# TPS5430.net
KiCad netlist of a schematic drawn in EasyEDA Pro
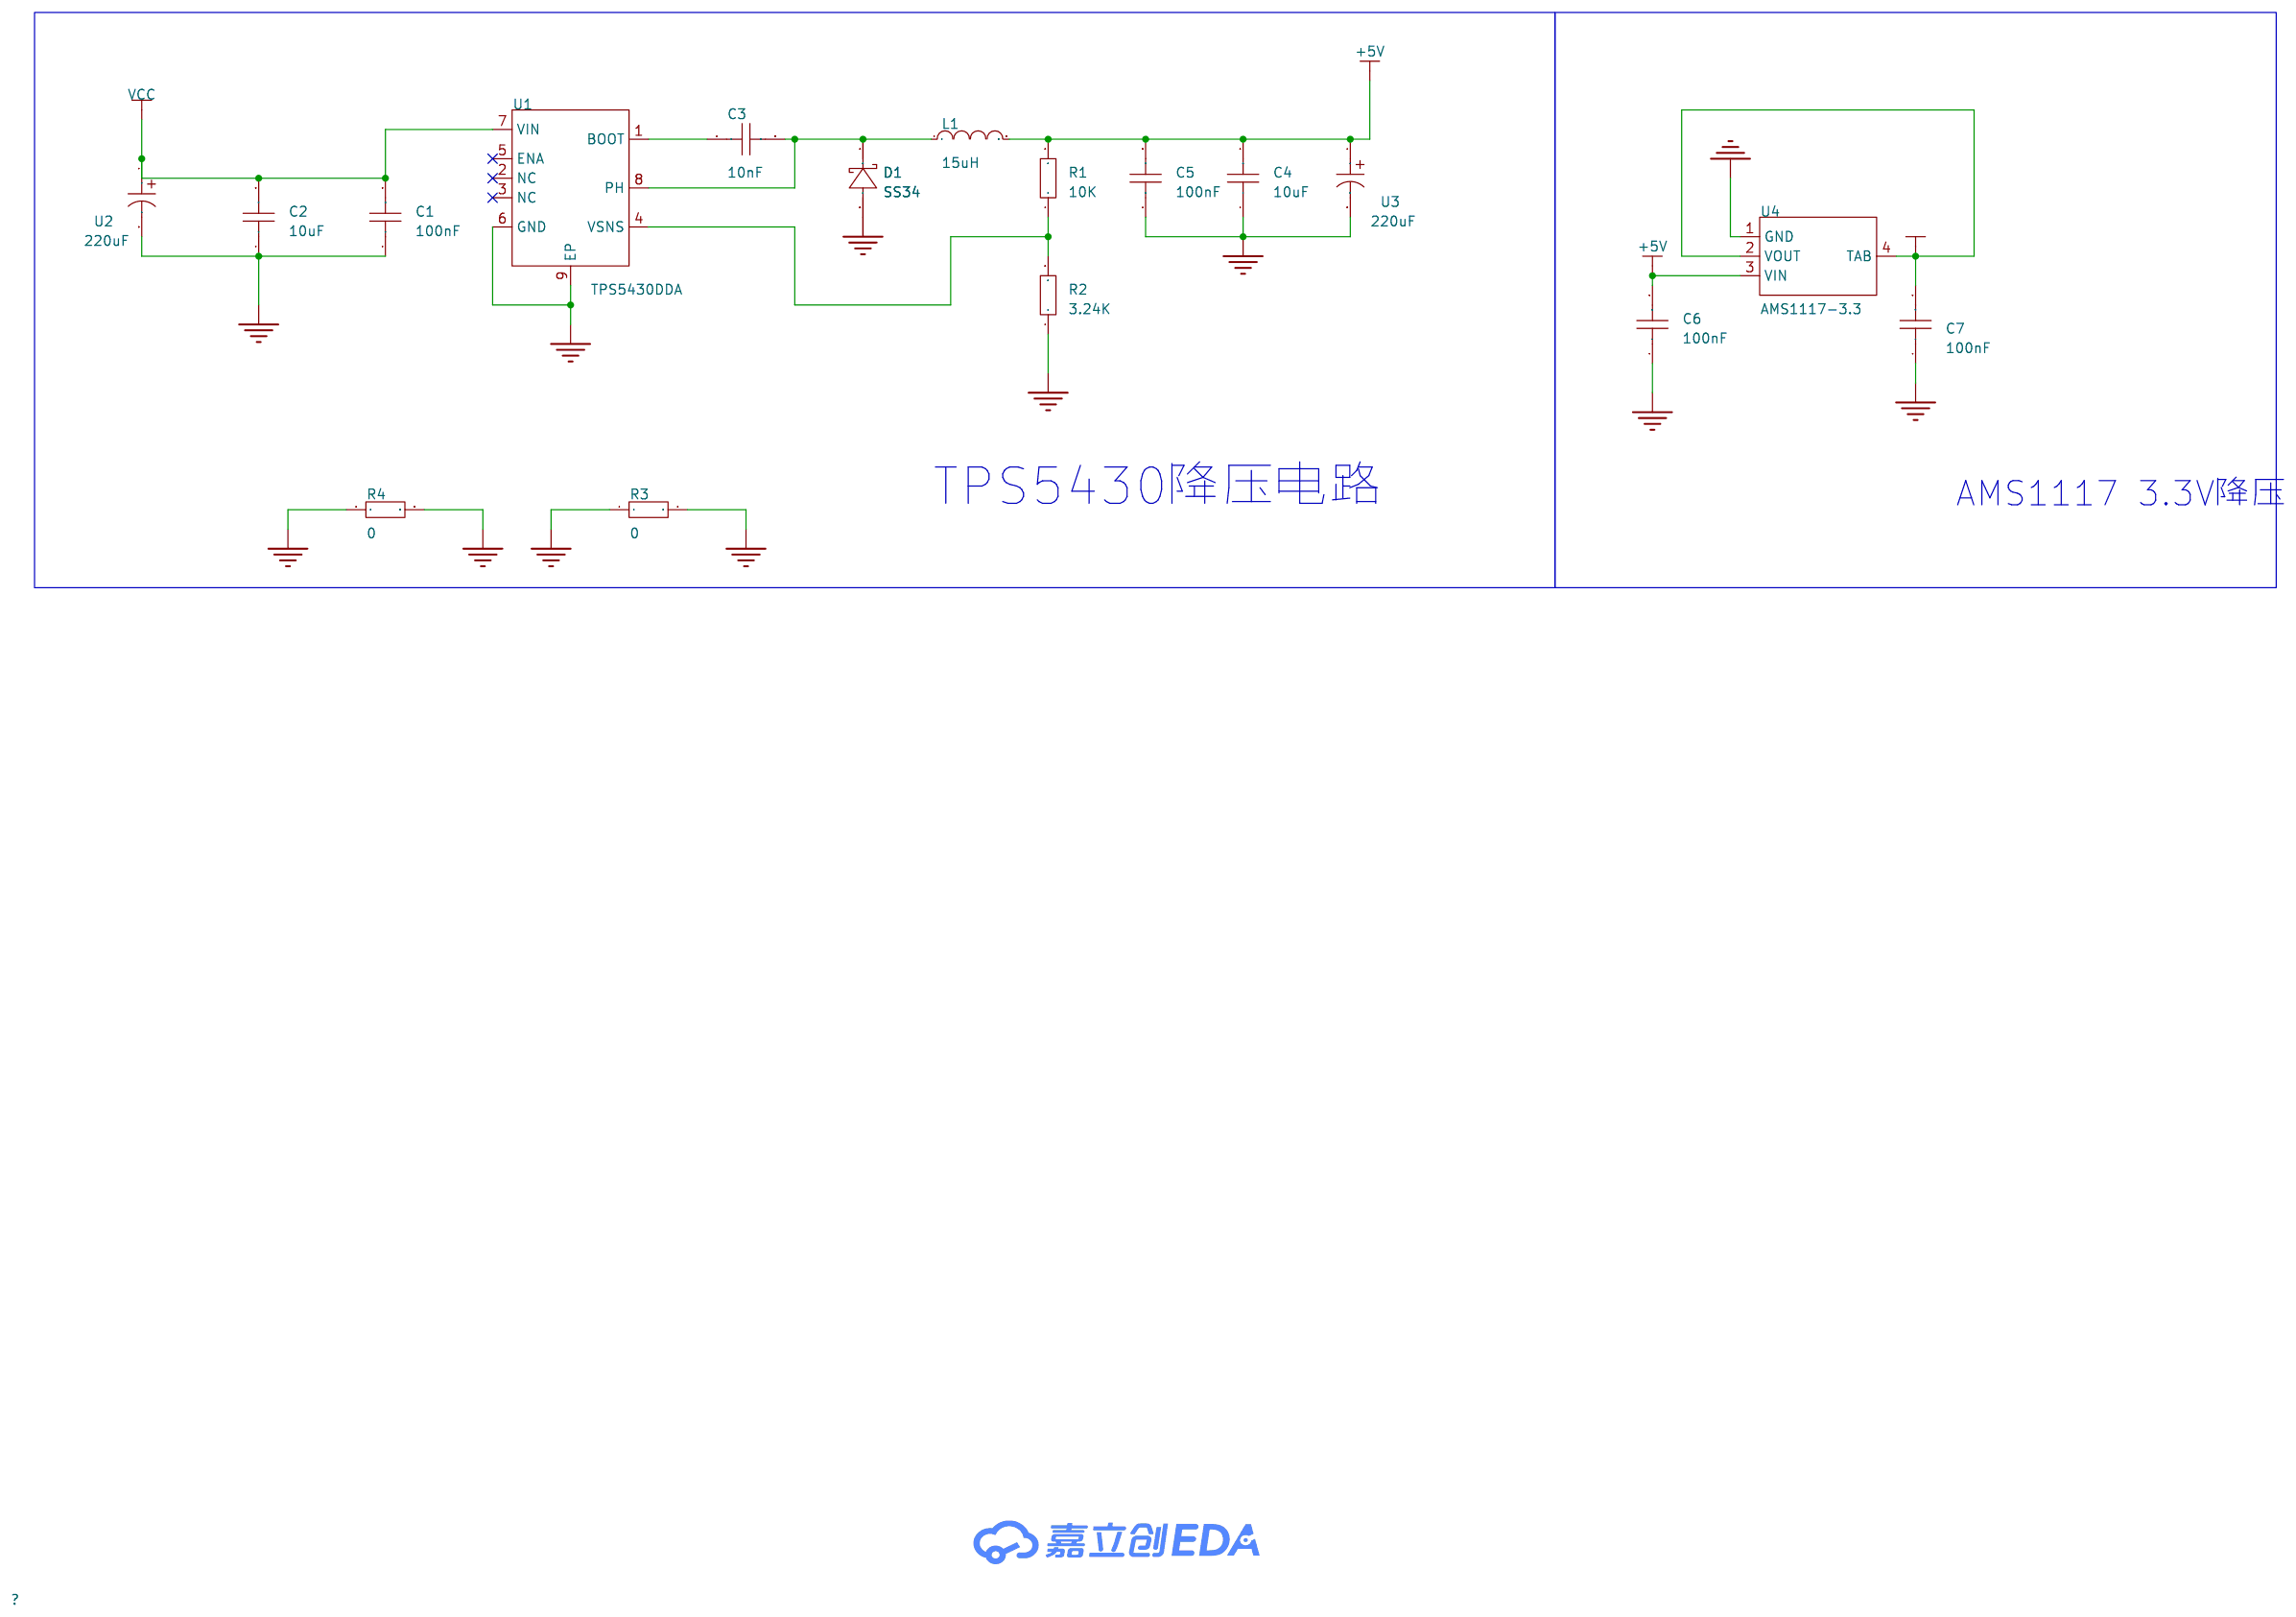
[diagram p0: schematic sheet]

(export (version "E")
  (design (tool "Eeschema 10.0.6"))
  (components
    (comp (ref "C1")
      (value "100nF")
      (footprint "easyedapro:C0603")
      (libsource (lib "easyedapro") (part "Capacitance"))
    )
    (comp (ref "C2")
      (value "10uF")
      (footprint "easyedapro:C0603")
      (libsource (lib "easyedapro") (part "Capacitance"))
    )
    (comp (ref "C3")
      (value "10nF")
      (footprint "easyedapro:C0402")
      (description "容值:100nF;精度:±10%;额定电压:50V;温度系数:X7R;")
      (fields
        (field (name "Manufacturer Part") "CL05B104KB54PNC")
        (field (name "Manufacturer") "SAMSUNG(三星)")
      )
      (libsource (lib "easyedapro") (part "CL05B104KB54PNC"))
    )
    (comp (ref "C4")
      (value "10uF")
      (footprint "easyedapro:C0603")
      (libsource (lib "easyedapro") (part "Capacitance"))
    )
    (comp (ref "C5")
      (value "100nF")
      (footprint "easyedapro:C0603")
      (libsource (lib "easyedapro") (part "Capacitance"))
    )
    (comp (ref "C6")
      (value "100nF")
      (footprint "easyedapro:C0402")
      (description "容值:100nF;精度:±10%;额定电压:50V;温度系数:X7R;")
      (fields
        (field (name "Manufacturer Part") "CL05B104KB54PNC")
        (field (name "Manufacturer") "SAMSUNG(三星)")
      )
      (libsource (lib "easyedapro") (part "CL05B104KB54PNC"))
    )
    (comp (ref "C7")
      (value "100nF")
      (footprint "easyedapro:C0402")
      (description "容值:100nF;精度:±10%;额定电压:50V;温度系数:X7R;")
      (fields
        (field (name "Manufacturer Part") "CL05B104KB54PNC")
        (field (name "Manufacturer") "SAMSUNG(三星)")
      )
      (libsource (lib "easyedapro") (part "CL05B104KB54PNC"))
    )
    (comp (ref "D1")
      (value "SS34")
      (footprint "easyedapro:SMA_L4.3-W2.5-LS5.0-RD")
      (description "二极管配置:独立式;正向压降(Vf):550mV@3A;直流反向耐压(Vr):40V;整流电流:3A;")
      (fields (field (name "Manufacturer") "TWGMC(台湾迪嘉)"))
      (libsource (lib "easyedapro") (part "SS34_C727060"))
    )
    (comp (ref "L1")
      (value "15uH")
      (footprint "easyedapro:IND-SMD_L7.0-W6.6_FXL0630")
      (description "电感值:15uH;精度:±20%;额定电流:3A;饱和电流(Isat):4A;类型:一体成型电感;")
      (fields (field (name "Manufacturer Part") "FXL0630-150-M") (field (name "Manufacturer") "cjiang(长江微电)"))
      (libsource (lib "easyedapro") (part "FXL0630-150-M"))
    )
    (comp (ref "R1") (value "10K") (footprint "easyedapro:R0805") (libsource (lib "easyedapro") (part "电阻")))
    (comp (ref "R2")
      (value "3.24K")
      (footprint "easyedapro:R0805")
      (libsource (lib "easyedapro") (part "电阻"))
    )
    (comp (ref "R3") (value "0") (footprint "easyedapro:R0805") (libsource (lib "easyedapro") (part "电阻")))
    (comp (ref "R4") (value "0") (footprint "easyedapro:R0805") (libsource (lib "easyedapro") (part "电阻")))
    (comp (ref "U1")
      (value "TPS5430DDA")
      (footprint "easyedapro:ESOP-8_L4.9-W3.9-P1.27-LS6.0-BL-EP-2")
      (description "功能类型:降压型;输出类型:可调;工作电压:5.5V~36V;输出电压:1.221V~32.04V;输出电流:3A;")
      (fields (field (name "Manufacturer") "TI(德州仪器)"))
      (libsource (lib "easyedapro") (part "TPS5430DDA"))
    )
    (comp (ref "U2")
      (value "220uF")
      (footprint "easyedapro:CAP-TH_BD6.3-P2.50-D0.5-FD")
      (description "容值:220uF;精度:±20%;额定电压:25V;纹波电流:236mA@120kHz;等效串联电阻(ESR):-;")
      (fields (field (name "Manufacturer Part") "KM1E221M0611") (field (name "Manufacturer") "ROQANG(容强)"))
      (libsource (lib "easyedapro") (part "KM1E221M0611"))
    )
    (comp (ref "U3")
      (value "220uF")
      (footprint "easyedapro:CAP-TH_BD6.3-P2.50-D0.5-FD")
      (description "容值:220uF;精度:±20%;额定电压:25V;纹波电流:236mA@120kHz;等效串联电阻(ESR):-;")
      (fields (field (name "Manufacturer Part") "KM1E221M0611") (field (name "Manufacturer") "ROQANG(容强)"))
      (libsource (lib "easyedapro") (part "KM1E221M0611"))
    )
    (comp (ref "U4")
      (value "AMS1117-3.3")
      (footprint "easyedapro:SOT-223-3_L6.5-W3.5-P3.05-LS7.0")
      (description "输出类型:固定;工作电压:12V;输出电压:3.3V;输出电流:1A;电源纹波抑制比(PSRR):70dB@(120Hz);输出极性:正极;")
      (fields (field (name "Manufacturer") "TWGMC(迪嘉)"))
      (libsource (lib "easyedapro") (part "AMS1117-3.3_C5250992"))
    )
  )
  (nets
    (net (code "1") (name "+3.3V") (class "Default")
      (node (ref "C7") (pin "2") (pinfunction "2_2") (pintype "unspecified"))
      (node (ref "U4") (pin "2") (pinfunction "VOUT_2") (pintype "unspecified"))
      (node (ref "U4") (pin "4") (pinfunction "TAB_4") (pintype "unspecified"))
    )
    (net (code "2") (name "+5V") (class "Default")
      (node (ref "C4") (pin "2") (pinfunction "2_2") (pintype "input"))
      (node (ref "C5") (pin "2") (pinfunction "2_2") (pintype "input"))
      (node (ref "C6") (pin "2") (pinfunction "2_2") (pintype "unspecified"))
      (node (ref "L1") (pin "2") (pinfunction "2_2") (pintype "unspecified"))
      (node (ref "R1") (pin "2") (pinfunction "2_2") (pintype "input"))
      (node (ref "U3") (pin "1") (pinfunction "1_1") (pintype "input"))
      (node (ref "U4") (pin "3") (pinfunction "VIN_3") (pintype "unspecified"))
    )
    (net (code "3") (name "GND") (class "Default")
      (node (ref "C1") (pin "1") (pinfunction "1_1") (pintype "input"))
      (node (ref "C2") (pin "1") (pinfunction "1_1") (pintype "input"))
      (node (ref "C4") (pin "1") (pinfunction "1_1") (pintype "input"))
      (node (ref "C5") (pin "1") (pinfunction "1_1") (pintype "input"))
      (node (ref "C6") (pin "1") (pinfunction "1_1") (pintype "unspecified"))
      (node (ref "C7") (pin "1") (pinfunction "1_1") (pintype "unspecified"))
      (node (ref "D1") (pin "2") (pinfunction "A_2") (pintype "unspecified"))
      (node (ref "R2") (pin "1") (pinfunction "1_1") (pintype "input"))
      (node (ref "R3") (pin "1") (pinfunction "1_1") (pintype "input"))
      (node (ref "R3") (pin "2") (pinfunction "2_2") (pintype "input"))
      (node (ref "R4") (pin "1") (pinfunction "1_1") (pintype "input"))
      (node (ref "R4") (pin "2") (pinfunction "2_2") (pintype "input"))
      (node (ref "U1") (pin "6") (pinfunction "GND_6") (pintype "unspecified"))
      (node (ref "U1") (pin "9") (pinfunction "EP_9") (pintype "unspecified"))
      (node (ref "U2") (pin "2") (pinfunction "2_2") (pintype "input"))
      (node (ref "U3") (pin "2") (pinfunction "2_2") (pintype "input"))
      (node (ref "U4") (pin "1") (pinfunction "GND_1") (pintype "unspecified"))
    )
    (net (code "4") (name "Net-(D1-C)") (class "Default")
      (node (ref "C3") (pin "2") (pinfunction "2_2") (pintype "unspecified"))
      (node (ref "D1") (pin "1") (pinfunction "C_1") (pintype "unspecified"))
      (node (ref "L1") (pin "1") (pinfunction "1_1") (pintype "unspecified"))
      (node (ref "U1") (pin "8") (pinfunction "PH_8") (pintype "unspecified"))
    )
    (net (code "5") (name "Net-(U1-BOOT)") (class "Default")
      (node (ref "C3") (pin "1") (pinfunction "1_1") (pintype "unspecified"))
      (node (ref "U1") (pin "1") (pinfunction "BOOT_1") (pintype "unspecified"))
    )
    (net (code "6") (name "Net-(U1-VSNS)") (class "Default")
      (node (ref "R1") (pin "1") (pinfunction "1_1") (pintype "input"))
      (node (ref "R2") (pin "2") (pinfunction "2_2") (pintype "input"))
      (node (ref "U1") (pin "4") (pinfunction "VSNS_4") (pintype "unspecified"))
    )
    (net (code "7") (name "VCC") (class "Default")
      (node (ref "C1") (pin "2") (pinfunction "2_2") (pintype "input"))
      (node (ref "C2") (pin "2") (pinfunction "2_2") (pintype "input"))
      (node (ref "U1") (pin "7") (pinfunction "VIN_7") (pintype "unspecified"))
      (node (ref "U2") (pin "1") (pinfunction "1_1") (pintype "input"))
    )
    (net (code "8") (name "unconnected-(U1-ENA-Pad5)") (class "Default")
      (node (ref "U1") (pin "5") (pinfunction "ENA_5") (pintype "unspecified+no_connect"))
    )
    (net (code "9") (name "unconnected-(U1-NC-Pad2)") (class "Default")
      (node (ref "U1") (pin "2") (pinfunction "NC_2") (pintype "unspecified+no_connect"))
    )
    (net (code "10") (name "unconnected-(U1-NC-Pad3)") (class "Default")
      (node (ref "U1") (pin "3") (pinfunction "NC_3") (pintype "unspecified+no_connect"))
    )
  )
)
